# board.net
KiCad netlist of a schematic drawn in EAGLE
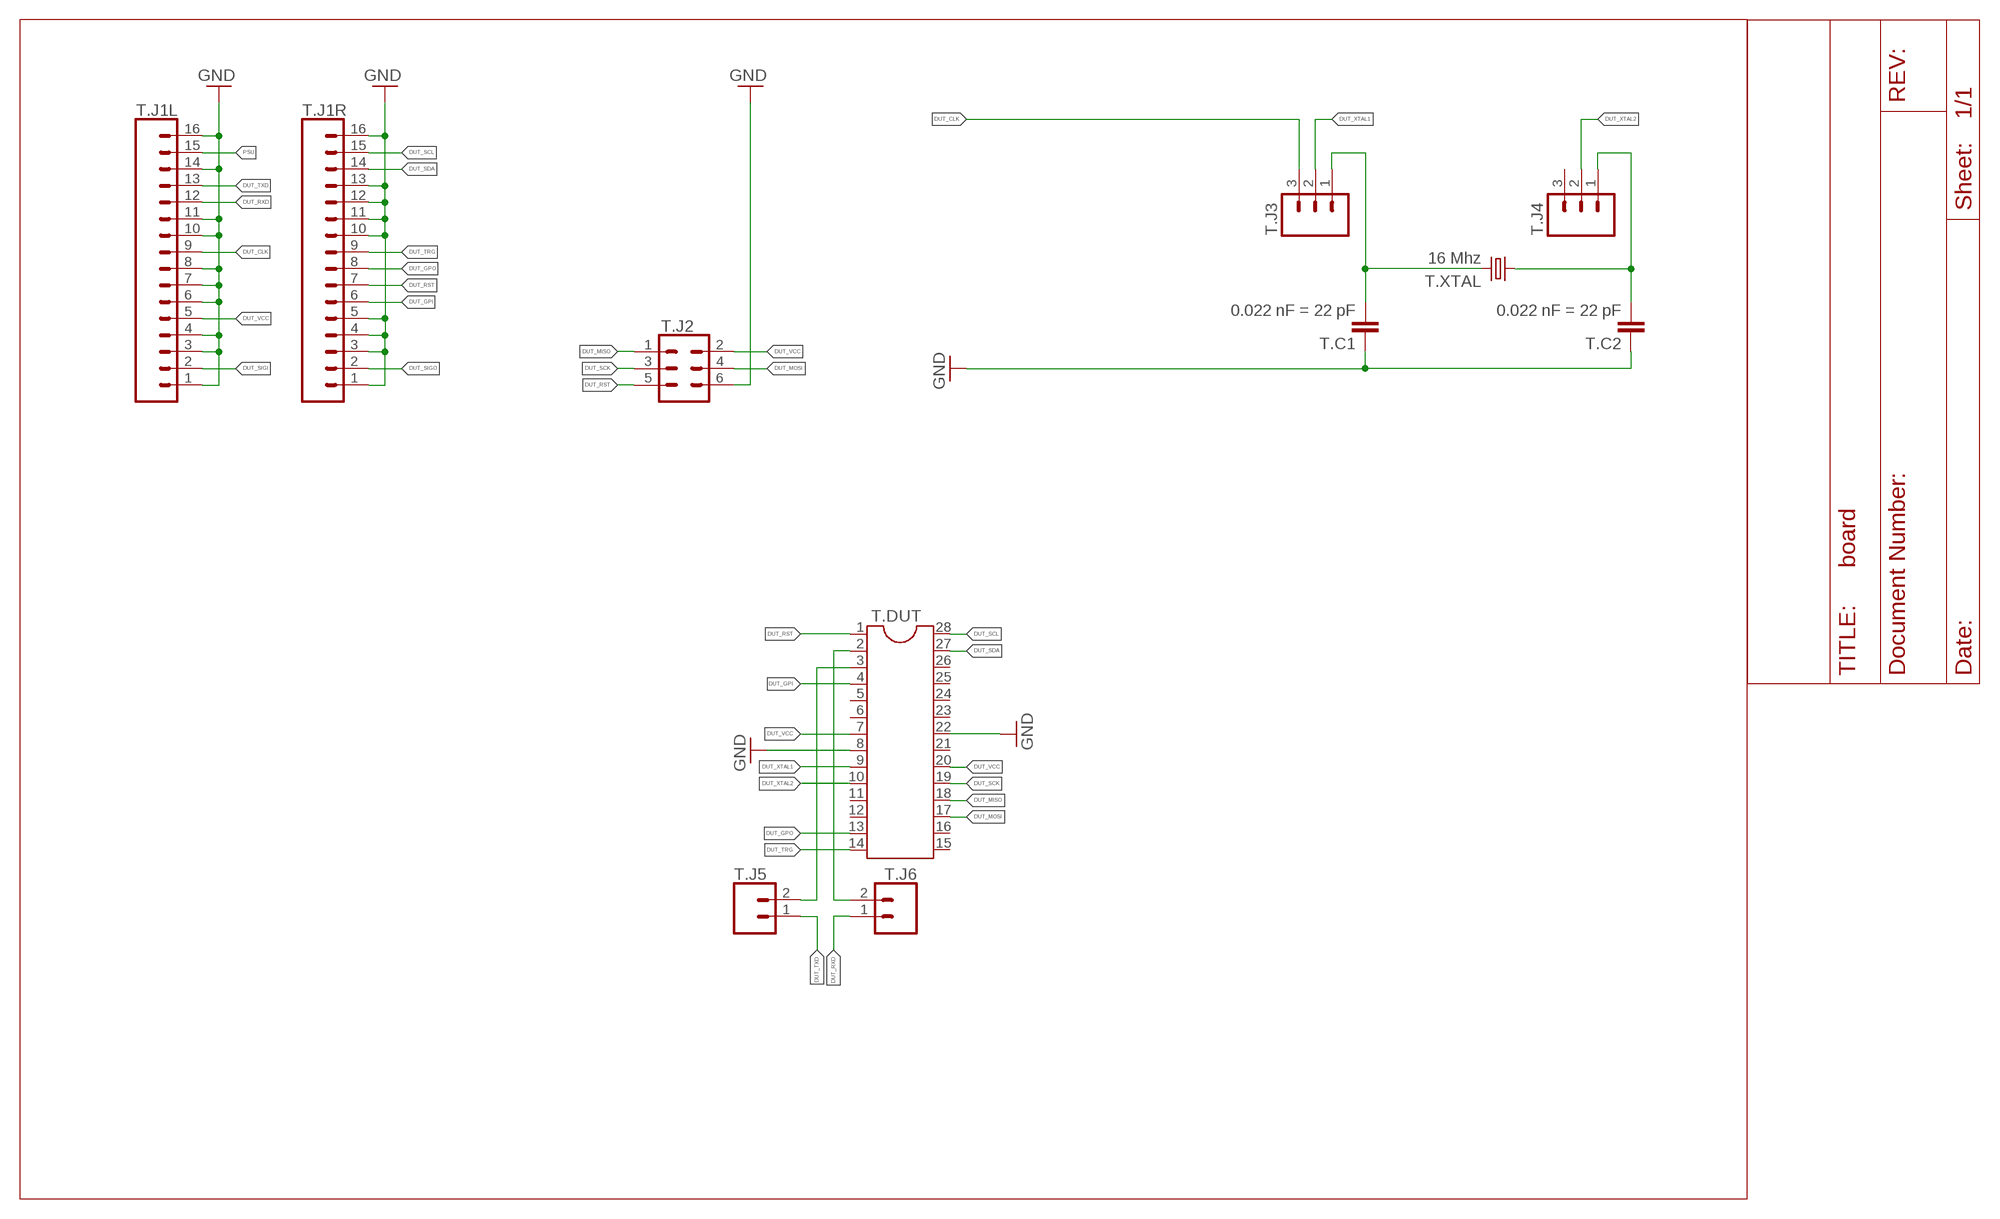
[diagram p0: schematic, sheet 1]

(export (version "E")
  (design (tool "Eeschema 10.0.6"))
  (components
    (comp (ref "T.C1")
      (value "0.022 nF = 22 pF")
      (footprint "eagle-import:0603-CAP")
      (libsource (lib "eagle-import") (part "CAP0603-CAP"))
    )
    (comp (ref "T.C2")
      (value "0.022 nF = 22 pF")
      (footprint "eagle-import:0603-CAP")
      (libsource (lib "eagle-import") (part "CAP0603-CAP"))
    )
    (comp (ref "T.DUT")
      (value "DIL28-3")
      (footprint "eagle-import:DIL28-3")
      (libsource (lib "eagle-import") (part "DIL28-3"))
    )
    (comp (ref "T.J1L")
      (value "CONN_16")
      (footprint "eagle-import:1X16")
      (libsource (lib "eagle-import") (part "CONN_16"))
    )
    (comp (ref "T.J1R")
      (value "CONN_16")
      (footprint "eagle-import:1X16")
      (libsource (lib "eagle-import") (part "CONN_16"))
    )
    (comp (ref "T.J2")
      (value "CONN_03X22X3_SILK_MALE_PTH")
      (footprint "eagle-import:2X3")
      (libsource (lib "eagle-import") (part "CONN_03X22X3_SILK_MALE_PTH"))
    )
    (comp (ref "T.J3")
      (value "M03PTH")
      (footprint "eagle-import:1X03")
      (libsource (lib "eagle-import") (part "M03PTH"))
    )
    (comp (ref "T.J4")
      (value "M03PTH")
      (footprint "eagle-import:1X03")
      (libsource (lib "eagle-import") (part "M03PTH"))
    )
    (comp (ref "T.J5")
      (value "CONN_02")
      (footprint "eagle-import:1X02")
      (libsource (lib "eagle-import") (part "CONN_02"))
    )
    (comp (ref "T.J6")
      (value "CONN_02")
      (footprint "eagle-import:1X02")
      (libsource (lib "eagle-import") (part "CONN_02"))
    )
    (comp (ref "T.XTAL")
      (value "16 Mhz")
      (footprint "eagle-import:HC49US")
      (libsource (lib "eagle-import") (part "CRYSTALHC49US"))
    )
  )
  (nets
    (net (code "1") (name "DUT_CLK") (class "Default")
      (node (ref "T.J1L") (pin "9") (pinfunction "9_9") (pintype "passive"))
      (node (ref "T.J3") (pin "3") (pinfunction "3_3") (pintype "passive"))
    )
    (net (code "2") (name "DUT_GPI") (class "Default")
      (node (ref "T.DUT") (pin "4") (pinfunction "4_4") (pintype "passive"))
      (node (ref "T.J1R") (pin "6") (pinfunction "6_6") (pintype "passive"))
    )
    (net (code "3") (name "DUT_GPO") (class "Default")
      (node (ref "T.DUT") (pin "13") (pinfunction "13_13") (pintype "passive"))
      (node (ref "T.J1R") (pin "8") (pinfunction "8_8") (pintype "passive"))
    )
    (net (code "4") (name "DUT_MISO") (class "Default")
      (node (ref "T.DUT") (pin "18") (pinfunction "18_18") (pintype "passive"))
      (node (ref "T.J2") (pin "1") (pinfunction "1_1") (pintype "bidirectional"))
    )
    (net (code "5") (name "DUT_MOSI") (class "Default")
      (node (ref "T.DUT") (pin "17") (pinfunction "17_17") (pintype "passive"))
      (node (ref "T.J2") (pin "4") (pinfunction "4_4") (pintype "bidirectional"))
    )
    (net (code "6") (name "DUT_RST") (class "Default")
      (node (ref "T.DUT") (pin "1") (pinfunction "1_1") (pintype "passive"))
      (node (ref "T.J1R") (pin "7") (pinfunction "7_7") (pintype "passive"))
      (node (ref "T.J2") (pin "5") (pinfunction "5_5") (pintype "bidirectional"))
    )
    (net (code "7") (name "DUT_RXD") (class "Default")
      (node (ref "T.J1L") (pin "12") (pinfunction "12_12") (pintype "passive"))
      (node (ref "T.J6") (pin "1") (pinfunction "1_1") (pintype "passive"))
    )
    (net (code "8") (name "DUT_SCK") (class "Default")
      (node (ref "T.DUT") (pin "19") (pinfunction "19_19") (pintype "passive"))
      (node (ref "T.J2") (pin "3") (pinfunction "3_3") (pintype "bidirectional"))
    )
    (net (code "9") (name "DUT_SCL") (class "Default")
      (node (ref "T.DUT") (pin "28") (pinfunction "28_28") (pintype "passive"))
      (node (ref "T.J1R") (pin "15") (pinfunction "15_15") (pintype "passive"))
    )
    (net (code "10") (name "DUT_SDA") (class "Default")
      (node (ref "T.DUT") (pin "27") (pinfunction "27_27") (pintype "passive"))
      (node (ref "T.J1R") (pin "14") (pinfunction "14_14") (pintype "passive"))
    )
    (net (code "11") (name "DUT_SIGI") (class "Default")
      (node (ref "T.J1L") (pin "2") (pinfunction "2_2") (pintype "passive"))
    )
    (net (code "12") (name "DUT_SIGO") (class "Default")
      (node (ref "T.J1R") (pin "2") (pinfunction "2_2") (pintype "passive"))
    )
    (net (code "13") (name "DUT_TRG") (class "Default")
      (node (ref "T.DUT") (pin "14") (pinfunction "14_14") (pintype "passive"))
      (node (ref "T.J1R") (pin "9") (pinfunction "9_9") (pintype "passive"))
    )
    (net (code "14") (name "DUT_TXD") (class "Default")
      (node (ref "T.J1L") (pin "13") (pinfunction "13_13") (pintype "passive"))
      (node (ref "T.J5") (pin "1") (pinfunction "1_1") (pintype "passive"))
    )
    (net (code "15") (name "DUT_VCC") (class "Default")
      (node (ref "T.DUT") (pin "20") (pinfunction "20_20") (pintype "passive"))
      (node (ref "T.DUT") (pin "7") (pinfunction "7_7") (pintype "passive"))
      (node (ref "T.J1L") (pin "5") (pinfunction "5_5") (pintype "passive"))
      (node (ref "T.J2") (pin "2") (pinfunction "2_2") (pintype "bidirectional"))
    )
    (net (code "16") (name "DUT_XTAL1") (class "Default")
      (node (ref "T.DUT") (pin "9") (pinfunction "9_9") (pintype "passive"))
      (node (ref "T.J3") (pin "2") (pinfunction "2_2") (pintype "passive"))
    )
    (net (code "17") (name "DUT_XTAL2") (class "Default")
      (node (ref "T.DUT") (pin "10") (pinfunction "10_10") (pintype "passive"))
      (node (ref "T.J4") (pin "2") (pinfunction "2_2") (pintype "passive"))
    )
    (net (code "18") (name "GND") (class "Default")
      (node (ref "T.C1") (pin "1") (pinfunction "1_1") (pintype "passive"))
      (node (ref "T.C2") (pin "1") (pinfunction "1_1") (pintype "passive"))
      (node (ref "T.DUT") (pin "22") (pinfunction "22_22") (pintype "passive"))
      (node (ref "T.DUT") (pin "8") (pinfunction "8_8") (pintype "passive"))
      (node (ref "T.J1L") (pin "1") (pinfunction "1_1") (pintype "passive"))
      (node (ref "T.J1L") (pin "10") (pinfunction "10_10") (pintype "passive"))
      (node (ref "T.J1L") (pin "11") (pinfunction "11_11") (pintype "passive"))
      (node (ref "T.J1L") (pin "14") (pinfunction "14_14") (pintype "passive"))
      (node (ref "T.J1L") (pin "16") (pinfunction "16_16") (pintype "passive"))
      (node (ref "T.J1L") (pin "3") (pinfunction "3_3") (pintype "passive"))
      (node (ref "T.J1L") (pin "4") (pinfunction "4_4") (pintype "passive"))
      (node (ref "T.J1L") (pin "6") (pinfunction "6_6") (pintype "passive"))
      (node (ref "T.J1L") (pin "7") (pinfunction "7_7") (pintype "passive"))
      (node (ref "T.J1L") (pin "8") (pinfunction "8_8") (pintype "passive"))
      (node (ref "T.J1R") (pin "1") (pinfunction "1_1") (pintype "passive"))
      (node (ref "T.J1R") (pin "10") (pinfunction "10_10") (pintype "passive"))
      (node (ref "T.J1R") (pin "11") (pinfunction "11_11") (pintype "passive"))
      (node (ref "T.J1R") (pin "12") (pinfunction "12_12") (pintype "passive"))
      (node (ref "T.J1R") (pin "13") (pinfunction "13_13") (pintype "passive"))
      (node (ref "T.J1R") (pin "16") (pinfunction "16_16") (pintype "passive"))
      (node (ref "T.J1R") (pin "3") (pinfunction "3_3") (pintype "passive"))
      (node (ref "T.J1R") (pin "4") (pinfunction "4_4") (pintype "passive"))
      (node (ref "T.J1R") (pin "5") (pinfunction "5_5") (pintype "passive"))
      (node (ref "T.J2") (pin "6") (pinfunction "6_6") (pintype "bidirectional"))
    )
    (net (code "19") (name "Net-(T.C1-Pad2)") (class "Default")
      (node (ref "T.C1") (pin "2") (pinfunction "2_2") (pintype "passive"))
      (node (ref "T.J3") (pin "1") (pinfunction "1_1") (pintype "passive"))
      (node (ref "T.XTAL") (pin "2") (pinfunction "2_2") (pintype "passive"))
    )
    (net (code "20") (name "Net-(T.C2-Pad2)") (class "Default")
      (node (ref "T.C2") (pin "2") (pinfunction "2_2") (pintype "passive"))
      (node (ref "T.J4") (pin "1") (pinfunction "1_1") (pintype "passive"))
      (node (ref "T.XTAL") (pin "1") (pinfunction "1_1") (pintype "passive"))
    )
    (net (code "21") (name "Net-(T.DUT-Pad2)") (class "Default")
      (node (ref "T.DUT") (pin "2") (pinfunction "2_2") (pintype "passive"))
      (node (ref "T.J6") (pin "2") (pinfunction "2_2") (pintype "passive"))
    )
    (net (code "22") (name "Net-(T.DUT-Pad3)") (class "Default")
      (node (ref "T.DUT") (pin "3") (pinfunction "3_3") (pintype "passive"))
      (node (ref "T.J5") (pin "2") (pinfunction "2_2") (pintype "passive"))
    )
    (net (code "23") (name "PSU") (class "Default")
      (node (ref "T.J1L") (pin "15") (pinfunction "15_15") (pintype "passive"))
    )
    (net (code "24") (name "unconnected-(T.DUT-Pad5)") (class "Default")
      (node (ref "T.DUT") (pin "5") (pinfunction "5_5") (pintype "passive"))
    )
    (net (code "25") (name "unconnected-(T.DUT-Pad6)") (class "Default")
      (node (ref "T.DUT") (pin "6") (pinfunction "6_6") (pintype "passive"))
    )
    (net (code "26") (name "unconnected-(T.DUT-Pad11)") (class "Default")
      (node (ref "T.DUT") (pin "11") (pinfunction "11_11") (pintype "passive"))
    )
    (net (code "27") (name "unconnected-(T.DUT-Pad12)") (class "Default")
      (node (ref "T.DUT") (pin "12") (pinfunction "12_12") (pintype "passive"))
    )
    (net (code "28") (name "unconnected-(T.DUT-Pad15)") (class "Default")
      (node (ref "T.DUT") (pin "15") (pinfunction "15_15") (pintype "passive"))
    )
    (net (code "29") (name "unconnected-(T.DUT-Pad16)") (class "Default")
      (node (ref "T.DUT") (pin "16") (pinfunction "16_16") (pintype "passive"))
    )
    (net (code "30") (name "unconnected-(T.DUT-Pad21)") (class "Default")
      (node (ref "T.DUT") (pin "21") (pinfunction "21_21") (pintype "passive"))
    )
    (net (code "31") (name "unconnected-(T.DUT-Pad23)") (class "Default")
      (node (ref "T.DUT") (pin "23") (pinfunction "23_23") (pintype "passive"))
    )
    (net (code "32") (name "unconnected-(T.DUT-Pad24)") (class "Default")
      (node (ref "T.DUT") (pin "24") (pinfunction "24_24") (pintype "passive"))
    )
    (net (code "33") (name "unconnected-(T.DUT-Pad25)") (class "Default")
      (node (ref "T.DUT") (pin "25") (pinfunction "25_25") (pintype "passive"))
    )
    (net (code "34") (name "unconnected-(T.DUT-Pad26)") (class "Default")
      (node (ref "T.DUT") (pin "26") (pinfunction "26_26") (pintype "passive"))
    )
    (net (code "35") (name "unconnected-(T.J4-Pad3)") (class "Default")
      (node (ref "T.J4") (pin "3") (pinfunction "3_3") (pintype "passive"))
    )
  )
)
